# ATtiny_45_and_85_programmer_shield.net
KiCad netlist of a schematic drawn in EAGLE
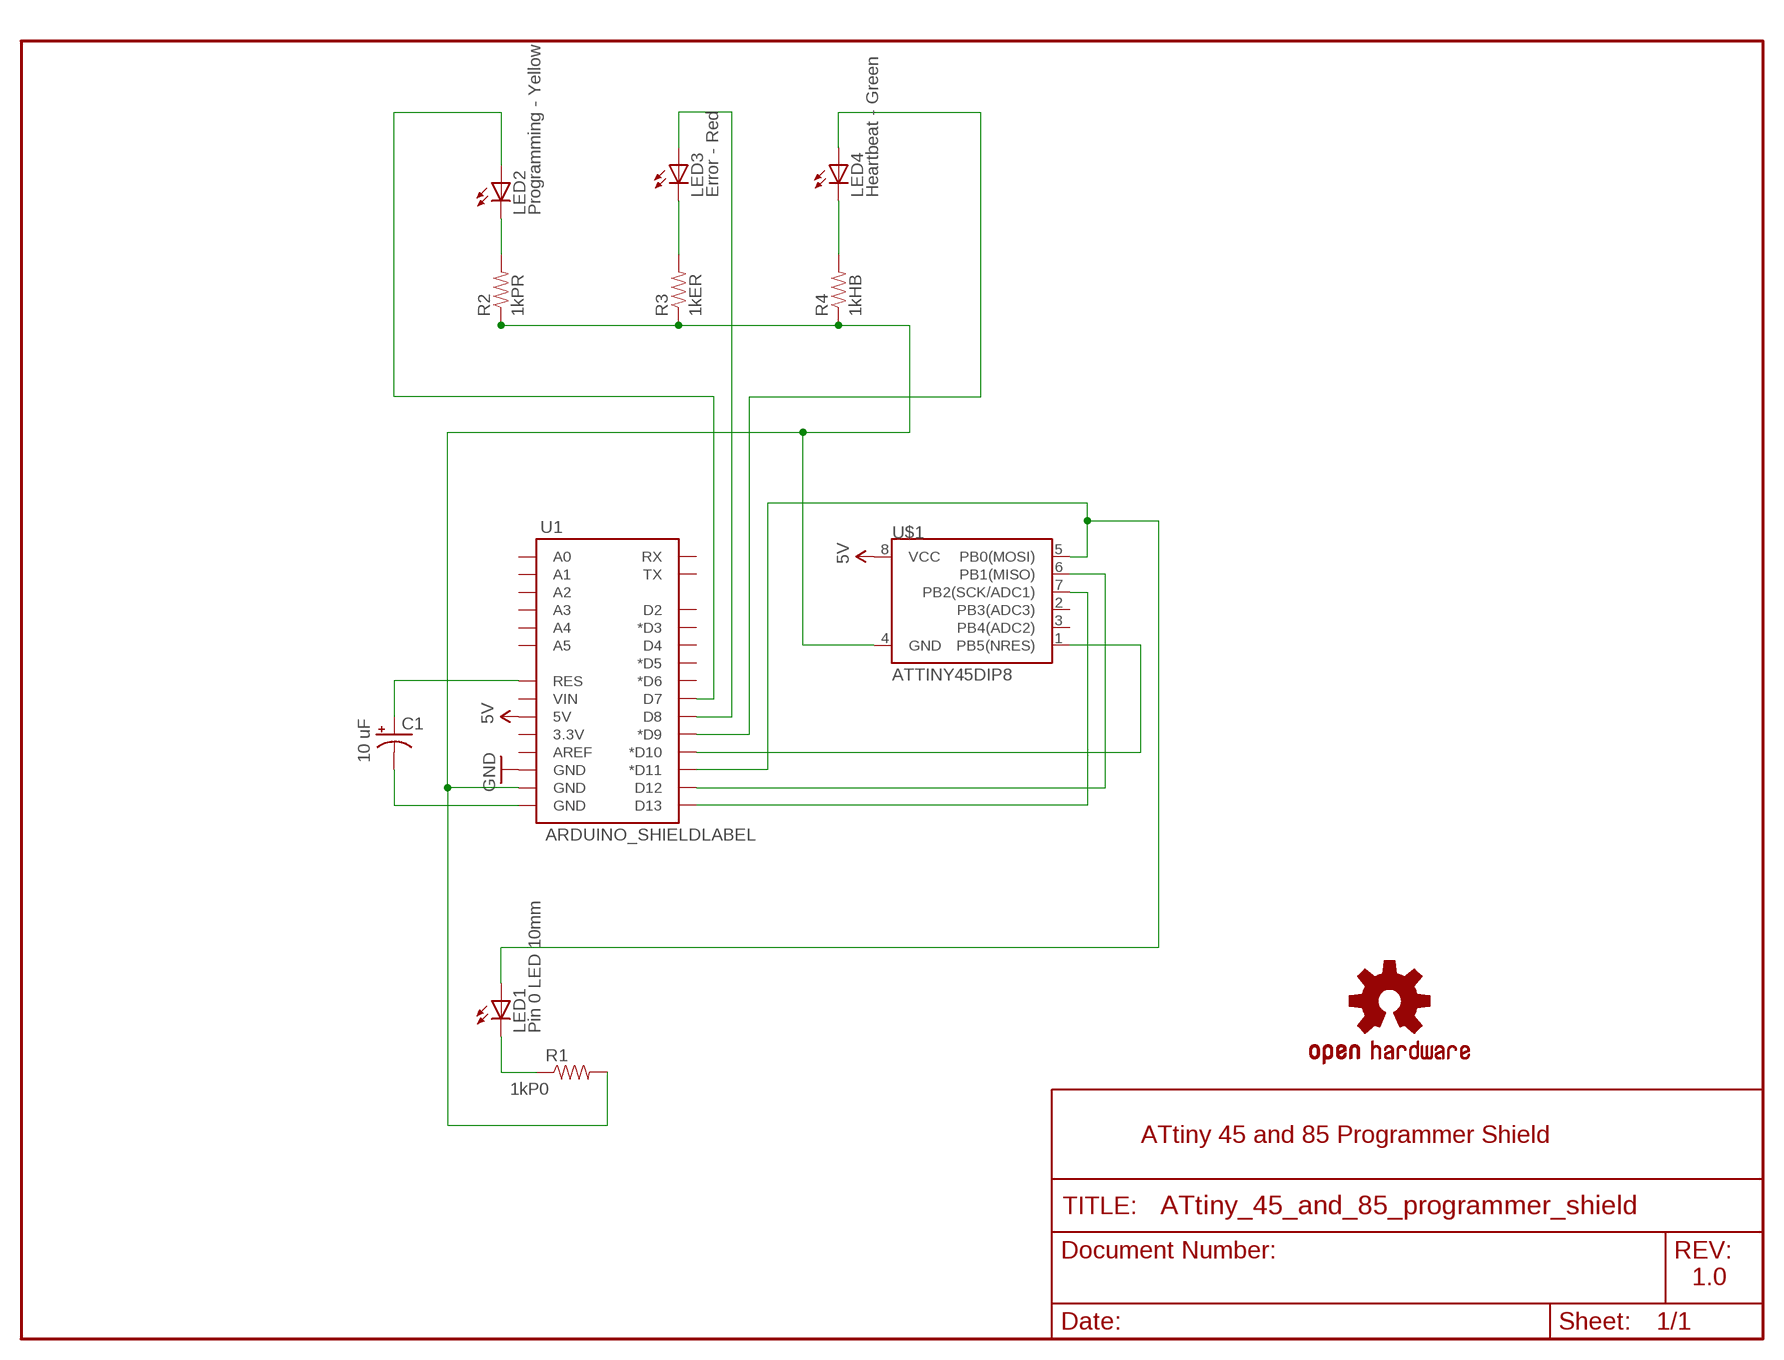
[diagram p0: schematic, sheet 1]

(export (version "E")
  (design (tool "Eeschema 10.0.6"))
  (components
    (comp (ref "C1")
      (value "10 uF")
      (footprint "eagle-import:CPOL-RADIAL-10UF-25V")
      (libsource (lib "eagle-import") (part "CAP_POLPTH2"))
    )
    (comp (ref "LED1")
      (value "Pin 0 LED 10mm")
      (footprint "eagle-import:LED10MM")
      (libsource (lib "eagle-import") (part "LED10MM"))
    )
    (comp (ref "LED2")
      (value "Programming - Yellow")
      (footprint "eagle-import:LED5MM")
      (libsource (lib "eagle-import") (part "LED5MM"))
    )
    (comp (ref "LED3")
      (value "Error - Red")
      (footprint "eagle-import:LED5MM")
      (libsource (lib "eagle-import") (part "LED5MM"))
    )
    (comp (ref "LED4")
      (value "Heartbeat - Green")
      (footprint "eagle-import:LED5MM")
      (libsource (lib "eagle-import") (part "LED5MM"))
    )
    (comp (ref "R1")
      (value "1kP0")
      (footprint "eagle-import:1_6W-RES")
      (libsource (lib "eagle-import") (part "RESISTORPTH-1/6W"))
    )
    (comp (ref "R2")
      (value "1kPR")
      (footprint "eagle-import:1_6W-RES")
      (libsource (lib "eagle-import") (part "RESISTORPTH-1/6W"))
    )
    (comp (ref "R3")
      (value "1kER")
      (footprint "eagle-import:1_6W-RES")
      (libsource (lib "eagle-import") (part "RESISTORPTH-1/6W"))
    )
    (comp (ref "R4")
      (value "1kHB")
      (footprint "eagle-import:1_6W-RES")
      (libsource (lib "eagle-import") (part "RESISTORPTH-1/6W"))
    )
    (comp (ref "U$1")
      (value "ATTINY45DIP8")
      (footprint "eagle-import:DIP08")
      (libsource (lib "eagle-import") (part "ATTINY45DIP8"))
    )
    (comp (ref "U$4")
      (value "OSHW-LOGOL")
      (footprint "eagle-import:OSHW-LOGO-L")
      (libsource (lib "eagle-import") (part "OSHW-LOGOL"))
    )
    (comp (ref "U1")
      (value "ARDUINO_SHIELDLABEL")
      (footprint "eagle-import:DUEMILANOVE_SHIELD")
      (libsource (lib "eagle-import") (part "ARDUINO_SHIELDLABEL"))
    )
  )
  (nets
    (net (code "1") (name "5V") (class "Default")
      (node (ref "U$1") (pin "8") (pinfunction "VCC_8") (pintype "bidirectional"))
      (node (ref "U1") (pin "5V") (pinfunction "5V_5V") (pintype "bidirectional"))
    )
    (net (code "2") (name "GND") (class "Default")
      (node (ref "U1") (pin "GND@2") (pinfunction "GND_GND@2") (pintype "bidirectional"))
    )
    (net (code "3") (name "Net-(C1-+)") (class "Default")
      (node (ref "C1") (pin "1") (pinfunction "+_1") (pintype "passive"))
      (node (ref "U1") (pin "RES") (pinfunction "RES_RES") (pintype "bidirectional"))
    )
    (net (code "4") (name "Net-(C1--)") (class "Default")
      (node (ref "C1") (pin "2") (pinfunction "-_2") (pintype "passive"))
      (node (ref "U1") (pin "GND@0") (pinfunction "GND_GND@0") (pintype "bidirectional"))
    )
    (net (code "5") (name "Net-(LED1-PadC)") (class "Default")
      (node (ref "LED1") (pin "C") (pinfunction "C_C") (pintype "passive"))
      (node (ref "R1") (pin "1") (pinfunction "1_1") (pintype "passive"))
    )
    (net (code "6") (name "Net-(LED2-C)") (class "Default")
      (node (ref "LED2") (pin "K") (pinfunction "C_K") (pintype "passive"))
      (node (ref "R2") (pin "2") (pinfunction "2_2") (pintype "passive"))
    )
    (net (code "7") (name "Net-(LED2-PadA)") (class "Default")
      (node (ref "LED2") (pin "A") (pinfunction "A_A") (pintype "passive"))
      (node (ref "U1") (pin "D7") (pinfunction "D7_D7") (pintype "bidirectional"))
    )
    (net (code "8") (name "Net-(LED3-C)") (class "Default")
      (node (ref "LED3") (pin "K") (pinfunction "C_K") (pintype "passive"))
      (node (ref "R3") (pin "2") (pinfunction "2_2") (pintype "passive"))
    )
    (net (code "9") (name "Net-(LED3-PadA)") (class "Default")
      (node (ref "LED3") (pin "A") (pinfunction "A_A") (pintype "passive"))
      (node (ref "U1") (pin "D8") (pinfunction "D8_D8") (pintype "bidirectional"))
    )
    (net (code "10") (name "Net-(LED4-C)") (class "Default")
      (node (ref "LED4") (pin "K") (pinfunction "C_K") (pintype "passive"))
      (node (ref "R4") (pin "2") (pinfunction "2_2") (pintype "passive"))
    )
    (net (code "11") (name "Net-(U$1-GND)") (class "Default")
      (node (ref "R1") (pin "2") (pinfunction "2_2") (pintype "passive"))
      (node (ref "R2") (pin "1") (pinfunction "1_1") (pintype "passive"))
      (node (ref "R3") (pin "1") (pinfunction "1_1") (pintype "passive"))
      (node (ref "R4") (pin "1") (pinfunction "1_1") (pintype "passive"))
      (node (ref "U$1") (pin "4") (pinfunction "GND_4") (pintype "bidirectional"))
      (node (ref "U1") (pin "GND@1") (pinfunction "GND_GND@1") (pintype "bidirectional"))
    )
    (net (code "12") (name "Net-(U$1-PB0(MOSI))") (class "Default")
      (node (ref "LED1") (pin "A") (pinfunction "A_A") (pintype "passive"))
      (node (ref "U$1") (pin "5") (pinfunction "PB0(MOSI)_5") (pintype "bidirectional"))
      (node (ref "U1") (pin "D11") (pinfunction "*D11_D11") (pintype "bidirectional"))
    )
    (net (code "13") (name "Net-(U$1-PB1(MISO))") (class "Default")
      (node (ref "U$1") (pin "6") (pinfunction "PB1(MISO)_6") (pintype "bidirectional"))
      (node (ref "U1") (pin "D12") (pinfunction "D12_D12") (pintype "bidirectional"))
    )
    (net (code "14") (name "Net-(U$1-PB2(SCK{slash}ADC1))") (class "Default")
      (node (ref "U$1") (pin "7") (pinfunction "PB2(SCK/ADC1)_7") (pintype "bidirectional"))
      (node (ref "U1") (pin "D13") (pinfunction "D13_D13") (pintype "bidirectional"))
    )
    (net (code "15") (name "Net-(U$1-PB5(NRES))") (class "Default")
      (node (ref "U$1") (pin "1") (pinfunction "PB5(NRES)_1") (pintype "bidirectional"))
      (node (ref "U1") (pin "D10") (pinfunction "*D10_D10") (pintype "bidirectional"))
    )
    (net (code "16") (name "Net-(U1-*D9)") (class "Default")
      (node (ref "LED4") (pin "A") (pinfunction "A_A") (pintype "passive"))
      (node (ref "U1") (pin "D9") (pinfunction "*D9_D9") (pintype "bidirectional"))
    )
    (net (code "17") (name "unconnected-(U$1-PB3(ADC3)-Pad2)") (class "Default")
      (node (ref "U$1") (pin "2") (pinfunction "PB3(ADC3)_2") (pintype "bidirectional"))
    )
    (net (code "18") (name "unconnected-(U$1-PB4(ADC2)-Pad3)") (class "Default")
      (node (ref "U$1") (pin "3") (pinfunction "PB4(ADC2)_3") (pintype "bidirectional"))
    )
    (net (code "19") (name "unconnected-(U1-*D3-PadD3)") (class "Default")
      (node (ref "U1") (pin "D3") (pinfunction "*D3_D3") (pintype "bidirectional"))
    )
    (net (code "20") (name "unconnected-(U1-*D5-PadD5)") (class "Default")
      (node (ref "U1") (pin "D5") (pinfunction "*D5_D5") (pintype "bidirectional"))
    )
    (net (code "21") (name "unconnected-(U1-*D6-PadD6)") (class "Default")
      (node (ref "U1") (pin "D6") (pinfunction "*D6_D6") (pintype "bidirectional"))
    )
    (net (code "22") (name "unconnected-(U1-Pad3.3V)") (class "Default")
      (node (ref "U1") (pin "3.3V") (pinfunction "3.3V_3.3V") (pintype "bidirectional"))
    )
    (net (code "23") (name "unconnected-(U1-PadA0)") (class "Default")
      (node (ref "U1") (pin "A0") (pinfunction "A0_A0") (pintype "bidirectional"))
    )
    (net (code "24") (name "unconnected-(U1-PadA1)") (class "Default")
      (node (ref "U1") (pin "A1") (pinfunction "A1_A1") (pintype "bidirectional"))
    )
    (net (code "25") (name "unconnected-(U1-PadA2)") (class "Default")
      (node (ref "U1") (pin "A2") (pinfunction "A2_A2") (pintype "bidirectional"))
    )
    (net (code "26") (name "unconnected-(U1-PadA3)") (class "Default")
      (node (ref "U1") (pin "A3") (pinfunction "A3_A3") (pintype "bidirectional"))
    )
    (net (code "27") (name "unconnected-(U1-PadA4)") (class "Default")
      (node (ref "U1") (pin "A4") (pinfunction "A4_A4") (pintype "bidirectional"))
    )
    (net (code "28") (name "unconnected-(U1-PadA5)") (class "Default")
      (node (ref "U1") (pin "A5") (pinfunction "A5_A5") (pintype "bidirectional"))
    )
    (net (code "29") (name "unconnected-(U1-PadAREF)") (class "Default")
      (node (ref "U1") (pin "AREF") (pinfunction "AREF_AREF") (pintype "bidirectional"))
    )
    (net (code "30") (name "unconnected-(U1-PadD2)") (class "Default")
      (node (ref "U1") (pin "D2") (pinfunction "D2_D2") (pintype "bidirectional"))
    )
    (net (code "31") (name "unconnected-(U1-PadD4)") (class "Default")
      (node (ref "U1") (pin "D4") (pinfunction "D4_D4") (pintype "bidirectional"))
    )
    (net (code "32") (name "unconnected-(U1-PadRX)") (class "Default")
      (node (ref "U1") (pin "RX") (pinfunction "RX_RX") (pintype "bidirectional"))
    )
    (net (code "33") (name "unconnected-(U1-PadTX)") (class "Default")
      (node (ref "U1") (pin "TX") (pinfunction "TX_TX") (pintype "bidirectional"))
    )
    (net (code "34") (name "unconnected-(U1-PadVIN)") (class "Default")
      (node (ref "U1") (pin "VIN") (pinfunction "VIN_VIN") (pintype "bidirectional"))
    )
  )
)
